# STC89LE.net
KiCad netlist of a schematic drawn in Altium Designer
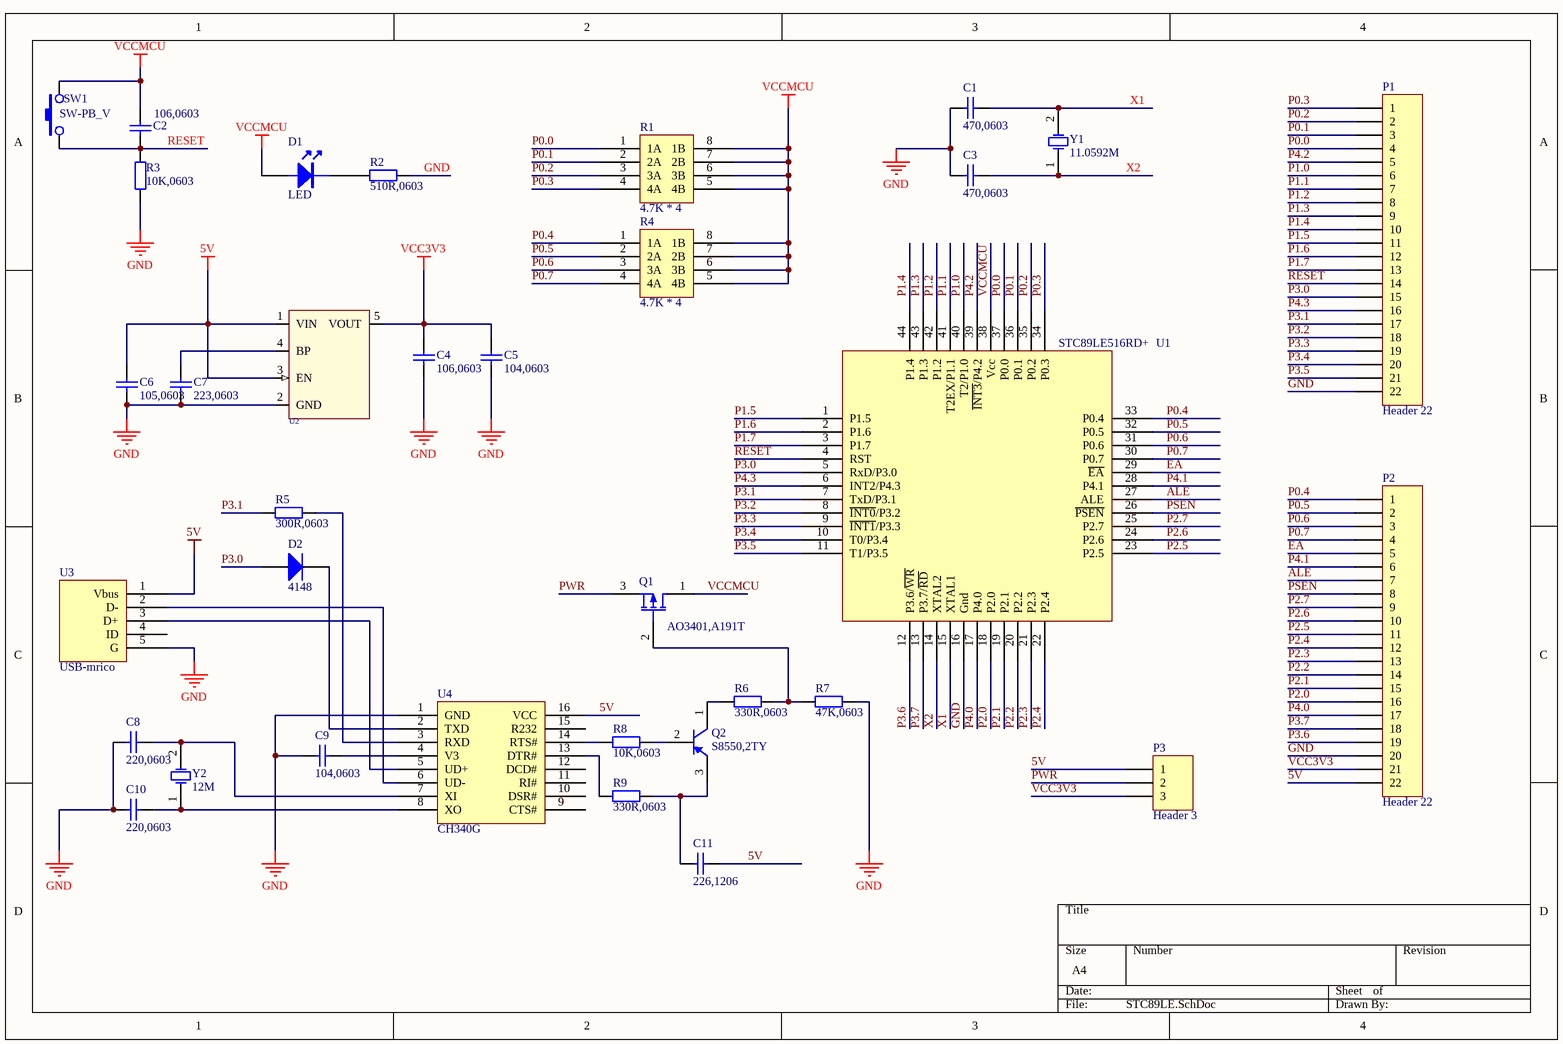
[diagram p0: STC89LE.SchDoc]

(export (version "E")
  (design (tool "Eeschema 10.0.6"))
  (components
    (comp (ref "C1")
      (value "470,0603")
      (footprint "C 0603")
      (description "Capacitor")
      (fields (field (name "PUBLISHER") "Altium Limited"))
      (libsource (lib "STM32F103C8T6") (part "Cap"))
    )
    (comp (ref "C2")
      (value "106,0603")
      (footprint "C 0603")
      (description "Capacitor")
      (fields (field (name "PUBLISHER") "Altium Limited"))
      (libsource (lib "STM32F103C8T6") (part "Cap"))
    )
    (comp (ref "C3")
      (value "470,0603")
      (footprint "C 0603")
      (description "Capacitor")
      (fields (field (name "PUBLISHER") "Altium Limited"))
      (libsource (lib "STM32F103C8T6") (part "Cap"))
    )
    (comp (ref "C4")
      (value "106,0603")
      (footprint "C 0603")
      (description "Capacitor")
      (fields (field (name "PUBLISHER") "Altium Limited"))
      (libsource (lib "STM32F103C8T6") (part "Cap"))
    )
    (comp (ref "C5")
      (value "104,0603")
      (footprint "C 0603")
      (description "Capacitor")
      (fields (field (name "PUBLISHER") "Altium Limited"))
      (libsource (lib "STM32F103C8T6") (part "Cap"))
    )
    (comp (ref "C6")
      (value "105,0603")
      (footprint "C 0603")
      (description "Capacitor")
      (fields (field (name "PUBLISHER") "Altium Limited"))
      (libsource (lib "STM32F103C8T6") (part "Cap"))
    )
    (comp (ref "C7")
      (value "223,0603")
      (footprint "C 0603")
      (description "Capacitor")
      (fields (field (name "PUBLISHER") "Altium Limited"))
      (libsource (lib "STM32F103C8T6") (part "Cap"))
    )
    (comp (ref "C8")
      (value "220,0603")
      (footprint "C 0603")
      (description "Capacitor")
      (fields (field (name "PUBLISHER") "Altium Limited"))
      (libsource (lib "STM32F103C8T6") (part "Cap"))
    )
    (comp (ref "C9")
      (value "104,0603")
      (footprint "C 0603")
      (description "Capacitor")
      (fields (field (name "PUBLISHER") "Altium Limited"))
      (libsource (lib "STM32F103C8T6") (part "Cap"))
    )
    (comp (ref "C10")
      (value "220,0603")
      (footprint "C 0603")
      (description "Capacitor")
      (fields (field (name "PUBLISHER") "Altium Limited"))
      (libsource (lib "STM32F103C8T6") (part "Cap"))
    )
    (comp (ref "C11")
      (value "226,1206")
      (footprint "C 3216")
      (description "Capacitor")
      (fields (field (name "PUBLISHER") "Altium Limited"))
      (libsource (lib "STM32F103C8T6") (part "Cap"))
    )
    (comp (ref "D1") (value "LED") (footprint "LED 0805G") (libsource (lib "STM32F103C8T6") (part "LED")))
    (comp (ref "D2")
      (value "4148")
      (footprint "DSO-C2/G1.6")
      (description "1 Amp General Purpose Rectifier")
      (fields (field (name "PUBLISHER") "Altium Limited"))
      (libsource (lib "Miscellaneous Devices") (part "Diode 1N4005"))
    )
    (comp (ref "P1")
      (value "Header 22")
      (footprint "HDR1X22")
      (description "Header, 22-Pin")
      (fields (field (name "PUBLISHER") "Altium Limited"))
      (libsource (lib "Miscellaneous Connectors") (part "Header 22"))
    )
    (comp (ref "P2")
      (value "Header 22")
      (footprint "HDR1X22")
      (description "Header, 22-Pin")
      (fields (field (name "PUBLISHER") "Altium Limited"))
      (libsource (lib "Miscellaneous Connectors") (part "Header 22"))
    )
    (comp (ref "P3")
      (value "Header 3")
      (footprint "HDR1X3")
      (description "Header, 3-Pin")
      (fields (field (name "PUBLISHER") "Altium Limited"))
      (libsource (lib "Miscellaneous Connectors") (part "Header 3"))
    )
    (comp (ref "Q1")
      (value "AO3401,A191T")
      (footprint "SOT23-3-MOS")
      (description "P-Channel MOSFET")
      (fields (field (name "PUBLISHER") "Altium Limited"))
      (libsource (lib "Miscellaneous Devices") (part "MOSFET-P"))
    )
    (comp (ref "Q2")
      (value "S8550,2TY")
      (footprint "SOT23-3-BJT")
      (description "PNP Bipolar Transistor")
      (fields (field (name "PUBLISHER") "Altium Limited"))
      (libsource (lib "Miscellaneous Devices") (part "PNP"))
    )
    (comp (ref "R1") (value "4.7K * 4") (footprint "8P4R 0603") (libsource (lib "PCB") (part "Res1")))
    (comp (ref "R2")
      (value "510R,0603")
      (footprint "R 0603")
      (description "Resistor")
      (fields (field (name "PUBLISHER") "Altium Limited"))
      (libsource (lib "") (part "Res2_1"))
    )
    (comp (ref "R3")
      (value "10K,0603")
      (footprint "R 0603")
      (description "Resistor")
      (fields (field (name "PUBLISHER") "Altium Limited"))
      (libsource (lib "") (part "Res2_2"))
    )
    (comp (ref "R4") (value "4.7K * 4") (footprint "8P4R 0603") (libsource (lib "PCB") (part "Res1")))
    (comp (ref "R5")
      (value "300R,0603")
      (footprint "R 0603")
      (description "Resistor")
      (fields (field (name "PUBLISHER") "Altium Limited"))
      (libsource (lib "STM32F103C8T6") (part "Res2"))
    )
    (comp (ref "R6")
      (value "330R,0603")
      (footprint "R 0603")
      (description "Resistor")
      (fields (field (name "PUBLISHER") "Altium Limited"))
      (libsource (lib "STM32F103C8T6") (part "Res2"))
    )
    (comp (ref "R7")
      (value "47K,0603")
      (footprint "R 0603")
      (description "Resistor")
      (fields (field (name "PUBLISHER") "Altium Limited"))
      (libsource (lib "STM32F103C8T6") (part "Res2"))
    )
    (comp (ref "R8")
      (value "10K,0603")
      (footprint "R 0603")
      (description "Resistor")
      (fields (field (name "PUBLISHER") "Altium Limited"))
      (libsource (lib "STM32F103C8T6") (part "Res2"))
    )
    (comp (ref "R9")
      (value "330R,0603")
      (footprint "R 0603")
      (description "Resistor")
      (fields (field (name "PUBLISHER") "Altium Limited"))
      (libsource (lib "STM32F103C8T6") (part "Res2"))
    )
    (comp (ref "SW1")
      (value "SW-PB_V")
      (footprint "TSW SMD-3*6*2.5")
      (description "SWITCH")
      (libsource (lib "STM32F103C8T6") (part "SW-PB_V"))
    )
    (comp (ref "U1")
      (value "STC89LE516RD+")
      (footprint "LQFP44")
      (libsource (lib "PCB") (part "STC89LE516RD+"))
    )
    (comp (ref "U2")
      (value "RT9193")
      (footprint "SOT23-5L")
      (fields (field (name "ICA_PARTNUM") "$$2191094$$RT9193-15CU5") (field (name "PART NUMBER") "TMP-13"))
      (libsource (lib "STM32F103C8T6") (part "RT9193X_5P"))
    )
    (comp (ref "U3")
      (value "USB-mrico")
      (footprint "USB-micro_B")
      (libsource (lib "PCB_Project_4") (part "usb-STM"))
    )
    (comp (ref "U4") (value "CH340G") (footprint "SOP16") (libsource (lib "PCB") (part "CH340G")))
    (comp (ref "Y1")
      (value "11.0592M")
      (footprint "STM32F103C8T6核心板:XTAL-5032")
      (description "Crystal Oscillator")
      (fields (field (name "PUBLISHER") "Altium Limited"))
      (libsource (lib "PCB_Project_4") (part "XTAL"))
    )
    (comp (ref "Y2")
      (value "12M")
      (footprint "STM32F103C8T6核心板:XTAL-5032")
      (description "Crystal Oscillator")
      (fields (field (name "PUBLISHER") "Altium Limited"))
      (libsource (lib "PCB_Project_4") (part "XTAL"))
    )
  )
  (nets
    (net (code "1") (name "/ALE") (class "Default")
      (node (ref "P2") (pin "7") (pinfunction "7_7") (pintype "passive"))
      (node (ref "U1") (pin "27") (pinfunction "ALE_27") (pintype "passive"))
    )
    (net (code "2") (name "/EA") (class "Default")
      (node (ref "P2") (pin "5") (pinfunction "5_5") (pintype "passive"))
      (node (ref "U1") (pin "29") (pinfunction "~{EA}_29") (pintype "passive"))
    )
    (net (code "3") (name "/P0.0") (class "Default")
      (node (ref "P1") (pin "4") (pinfunction "4_4") (pintype "passive"))
      (node (ref "R1") (pin "1") (pinfunction "1A_1") (pintype "passive"))
      (node (ref "U1") (pin "37") (pinfunction "P0.0_37") (pintype "passive"))
    )
    (net (code "4") (name "/P0.1") (class "Default")
      (node (ref "P1") (pin "3") (pinfunction "3_3") (pintype "passive"))
      (node (ref "R1") (pin "2") (pinfunction "2A_2") (pintype "passive"))
      (node (ref "U1") (pin "36") (pinfunction "P0.1_36") (pintype "passive"))
    )
    (net (code "5") (name "/P0.2") (class "Default")
      (node (ref "P1") (pin "2") (pinfunction "2_2") (pintype "passive"))
      (node (ref "R1") (pin "3") (pinfunction "3A_3") (pintype "passive"))
      (node (ref "U1") (pin "35") (pinfunction "P0.2_35") (pintype "passive"))
    )
    (net (code "6") (name "/P0.3") (class "Default")
      (node (ref "P1") (pin "1") (pinfunction "1_1") (pintype "passive"))
      (node (ref "R1") (pin "4") (pinfunction "4A_4") (pintype "passive"))
      (node (ref "U1") (pin "34") (pinfunction "P0.3_34") (pintype "passive"))
    )
    (net (code "7") (name "/P0.4") (class "Default")
      (node (ref "P2") (pin "1") (pinfunction "1_1") (pintype "passive"))
      (node (ref "R4") (pin "1") (pinfunction "1A_1") (pintype "passive"))
      (node (ref "U1") (pin "33") (pinfunction "P0.4_33") (pintype "passive"))
    )
    (net (code "8") (name "/P0.5") (class "Default")
      (node (ref "P2") (pin "2") (pinfunction "2_2") (pintype "passive"))
      (node (ref "R4") (pin "2") (pinfunction "2A_2") (pintype "passive"))
      (node (ref "U1") (pin "32") (pinfunction "P0.5_32") (pintype "passive"))
    )
    (net (code "9") (name "/P0.6") (class "Default")
      (node (ref "P2") (pin "3") (pinfunction "3_3") (pintype "passive"))
      (node (ref "R4") (pin "3") (pinfunction "3A_3") (pintype "passive"))
      (node (ref "U1") (pin "31") (pinfunction "P0.6_31") (pintype "passive"))
    )
    (net (code "10") (name "/P0.7") (class "Default")
      (node (ref "P2") (pin "4") (pinfunction "4_4") (pintype "passive"))
      (node (ref "R4") (pin "4") (pinfunction "4A_4") (pintype "passive"))
      (node (ref "U1") (pin "30") (pinfunction "P0.7_30") (pintype "passive"))
    )
    (net (code "11") (name "/P1.0") (class "Default")
      (node (ref "P1") (pin "6") (pinfunction "6_6") (pintype "passive"))
      (node (ref "U1") (pin "40") (pinfunction "T2/P1.0_40") (pintype "passive"))
    )
    (net (code "12") (name "/P1.1") (class "Default")
      (node (ref "P1") (pin "7") (pinfunction "7_7") (pintype "passive"))
      (node (ref "U1") (pin "41") (pinfunction "T2EX/P1.1_41") (pintype "passive"))
    )
    (net (code "13") (name "/P1.2") (class "Default")
      (node (ref "P1") (pin "8") (pinfunction "8_8") (pintype "passive"))
      (node (ref "U1") (pin "42") (pinfunction "P1.2_42") (pintype "passive"))
    )
    (net (code "14") (name "/P1.3") (class "Default")
      (node (ref "P1") (pin "9") (pinfunction "9_9") (pintype "passive"))
      (node (ref "U1") (pin "43") (pinfunction "P1.3_43") (pintype "passive"))
    )
    (net (code "15") (name "/P1.4") (class "Default")
      (node (ref "P1") (pin "10") (pinfunction "10_10") (pintype "passive"))
      (node (ref "U1") (pin "44") (pinfunction "P1.4_44") (pintype "passive"))
    )
    (net (code "16") (name "/P1.5") (class "Default")
      (node (ref "P1") (pin "11") (pinfunction "11_11") (pintype "passive"))
      (node (ref "U1") (pin "1") (pinfunction "P1.5_1") (pintype "passive"))
    )
    (net (code "17") (name "/P1.6") (class "Default")
      (node (ref "P1") (pin "12") (pinfunction "12_12") (pintype "passive"))
      (node (ref "U1") (pin "2") (pinfunction "P1.6_2") (pintype "passive"))
    )
    (net (code "18") (name "/P1.7") (class "Default")
      (node (ref "P1") (pin "13") (pinfunction "13_13") (pintype "passive"))
      (node (ref "U1") (pin "3") (pinfunction "P1.7_3") (pintype "passive"))
    )
    (net (code "19") (name "/P2.0") (class "Default")
      (node (ref "P2") (pin "16") (pinfunction "16_16") (pintype "passive"))
      (node (ref "U1") (pin "18") (pinfunction "P2.0_18") (pintype "passive"))
    )
    (net (code "20") (name "/P2.1") (class "Default")
      (node (ref "P2") (pin "15") (pinfunction "15_15") (pintype "passive"))
      (node (ref "U1") (pin "19") (pinfunction "P2.1_19") (pintype "passive"))
    )
    (net (code "21") (name "/P2.2") (class "Default")
      (node (ref "P2") (pin "14") (pinfunction "14_14") (pintype "passive"))
      (node (ref "U1") (pin "20") (pinfunction "P2.2_20") (pintype "passive"))
    )
    (net (code "22") (name "/P2.3") (class "Default")
      (node (ref "P2") (pin "13") (pinfunction "13_13") (pintype "passive"))
      (node (ref "U1") (pin "21") (pinfunction "P2.3_21") (pintype "passive"))
    )
    (net (code "23") (name "/P2.4") (class "Default")
      (node (ref "P2") (pin "12") (pinfunction "12_12") (pintype "passive"))
      (node (ref "U1") (pin "22") (pinfunction "P2.4_22") (pintype "passive"))
    )
    (net (code "24") (name "/P2.5") (class "Default")
      (node (ref "P2") (pin "11") (pinfunction "11_11") (pintype "passive"))
      (node (ref "U1") (pin "23") (pinfunction "P2.5_23") (pintype "passive"))
    )
    (net (code "25") (name "/P2.6") (class "Default")
      (node (ref "P2") (pin "10") (pinfunction "10_10") (pintype "passive"))
      (node (ref "U1") (pin "24") (pinfunction "P2.6_24") (pintype "passive"))
    )
    (net (code "26") (name "/P2.7") (class "Default")
      (node (ref "P2") (pin "9") (pinfunction "9_9") (pintype "passive"))
      (node (ref "U1") (pin "25") (pinfunction "P2.7_25") (pintype "passive"))
    )
    (net (code "27") (name "/P3.0") (class "Default")
      (node (ref "D2") (pin "1") (pinfunction "A_1") (pintype "passive"))
      (node (ref "P1") (pin "15") (pinfunction "15_15") (pintype "passive"))
      (node (ref "U1") (pin "5") (pinfunction "RxD/P3.0_5") (pintype "passive"))
    )
    (net (code "28") (name "/P3.1") (class "Default")
      (node (ref "P1") (pin "17") (pinfunction "17_17") (pintype "passive"))
      (node (ref "R5") (pin "2") (pinfunction "2_2") (pintype "passive"))
      (node (ref "U1") (pin "7") (pinfunction "TxD/P3.1_7") (pintype "passive"))
    )
    (net (code "29") (name "/P3.2") (class "Default")
      (node (ref "P1") (pin "18") (pinfunction "18_18") (pintype "passive"))
      (node (ref "U1") (pin "8") (pinfunction "~{INT0}/P3.2_8") (pintype "passive"))
    )
    (net (code "30") (name "/P3.3") (class "Default")
      (node (ref "P1") (pin "19") (pinfunction "19_19") (pintype "passive"))
      (node (ref "U1") (pin "9") (pinfunction "~{INT1}/P3.3_9") (pintype "passive"))
    )
    (net (code "31") (name "/P3.4") (class "Default")
      (node (ref "P1") (pin "20") (pinfunction "20_20") (pintype "passive"))
      (node (ref "U1") (pin "10") (pinfunction "T0/P3.4_10") (pintype "passive"))
    )
    (net (code "32") (name "/P3.5") (class "Default")
      (node (ref "P1") (pin "21") (pinfunction "21_21") (pintype "passive"))
      (node (ref "U1") (pin "11") (pinfunction "T1/P3.5_11") (pintype "passive"))
    )
    (net (code "33") (name "/P3.6") (class "Default")
      (node (ref "P2") (pin "19") (pinfunction "19_19") (pintype "passive"))
      (node (ref "U1") (pin "12") (pinfunction "P3.6/~{WR}_12") (pintype "passive"))
    )
    (net (code "34") (name "/P3.7") (class "Default")
      (node (ref "P2") (pin "18") (pinfunction "18_18") (pintype "passive"))
      (node (ref "U1") (pin "13") (pinfunction "P3.7/~{RD}_13") (pintype "passive"))
    )
    (net (code "35") (name "/P4.0") (class "Default")
      (node (ref "P2") (pin "17") (pinfunction "17_17") (pintype "passive"))
      (node (ref "U1") (pin "17") (pinfunction "P4.0_17") (pintype "passive"))
    )
    (net (code "36") (name "/P4.1") (class "Default")
      (node (ref "P2") (pin "6") (pinfunction "6_6") (pintype "passive"))
      (node (ref "U1") (pin "28") (pinfunction "P4.1_28") (pintype "passive"))
    )
    (net (code "37") (name "/P4.2") (class "Default")
      (node (ref "P1") (pin "5") (pinfunction "5_5") (pintype "passive"))
      (node (ref "U1") (pin "39") (pinfunction "~{INT3}/P4.2_39") (pintype "passive"))
    )
    (net (code "38") (name "/P4.3") (class "Default")
      (node (ref "P1") (pin "16") (pinfunction "16_16") (pintype "passive"))
      (node (ref "U1") (pin "6") (pinfunction "INT2/P4.3_6") (pintype "passive"))
    )
    (net (code "39") (name "/PSEN") (class "Default")
      (node (ref "P2") (pin "8") (pinfunction "8_8") (pintype "passive"))
      (node (ref "U1") (pin "26") (pinfunction "~{PSEN}_26") (pintype "passive"))
    )
    (net (code "40") (name "/PWR") (class "Default")
      (node (ref "P3") (pin "2") (pinfunction "2_2") (pintype "passive"))
      (node (ref "Q1") (pin "3") (pinfunction "S_3") (pintype "passive"))
    )
    (net (code "41") (name "/RESET") (class "Default")
      (node (ref "C2") (pin "1") (pinfunction "1_1") (pintype "passive"))
      (node (ref "P1") (pin "14") (pinfunction "14_14") (pintype "passive"))
      (node (ref "R3") (pin "2") (pinfunction "2_2") (pintype "passive"))
      (node (ref "SW1") (pin "1") (pinfunction "1_1") (pintype "passive"))
      (node (ref "U1") (pin "4") (pinfunction "RST_4") (pintype "passive"))
    )
    (net (code "42") (name "/X1") (class "Default")
      (node (ref "C1") (pin "1") (pinfunction "1_1") (pintype "passive"))
      (node (ref "U1") (pin "15") (pinfunction "XTAL1_15") (pintype "passive"))
      (node (ref "Y1") (pin "2") (pinfunction "OSC2_2") (pintype "passive"))
    )
    (net (code "43") (name "/X2") (class "Default")
      (node (ref "C3") (pin "1") (pinfunction "1_1") (pintype "passive"))
      (node (ref "U1") (pin "14") (pinfunction "XTAL2_14") (pintype "passive"))
      (node (ref "Y1") (pin "1") (pinfunction "OSC1_1") (pintype "passive"))
    )
    (net (code "44") (name "5V") (class "Default")
      (node (ref "C11") (pin "1") (pinfunction "1_1") (pintype "passive"))
      (node (ref "C6") (pin "2") (pinfunction "2_2") (pintype "passive"))
      (node (ref "P2") (pin "22") (pinfunction "22_22") (pintype "passive"))
      (node (ref "P3") (pin "1") (pinfunction "1_1") (pintype "passive"))
      (node (ref "U2") (pin "1") (pinfunction "VIN_1") (pintype "power_in"))
      (node (ref "U2") (pin "3") (pinfunction "EN_3") (pintype "input"))
      (node (ref "U3") (pin "1") (pinfunction "Vbus_1") (pintype "passive"))
      (node (ref "U4") (pin "16") (pinfunction "VCC_16") (pintype "passive"))
    )
    (net (code "45") (name "GND") (class "Default")
      (node (ref "C1") (pin "2") (pinfunction "2_2") (pintype "passive"))
      (node (ref "C10") (pin "2") (pinfunction "2_2") (pintype "passive"))
      (node (ref "C3") (pin "2") (pinfunction "2_2") (pintype "passive"))
      (node (ref "C4") (pin "2") (pinfunction "2_2") (pintype "passive"))
      (node (ref "C5") (pin "1") (pinfunction "1_1") (pintype "passive"))
      (node (ref "C6") (pin "1") (pinfunction "1_1") (pintype "passive"))
      (node (ref "C7") (pin "1") (pinfunction "1_1") (pintype "passive"))
      (node (ref "C8") (pin "2") (pinfunction "2_2") (pintype "passive"))
      (node (ref "C9") (pin "2") (pinfunction "2_2") (pintype "passive"))
      (node (ref "P1") (pin "22") (pinfunction "22_22") (pintype "passive"))
      (node (ref "P2") (pin "20") (pinfunction "20_20") (pintype "passive"))
      (node (ref "R2") (pin "2") (pinfunction "2_2") (pintype "passive"))
      (node (ref "R3") (pin "1") (pinfunction "1_1") (pintype "passive"))
      (node (ref "R7") (pin "1") (pinfunction "1_1") (pintype "passive"))
      (node (ref "U1") (pin "16") (pinfunction "Gnd_16") (pintype "passive"))
      (node (ref "U2") (pin "2") (pinfunction "GND_2") (pintype "power_in"))
      (node (ref "U3") (pin "5") (pinfunction "G_5") (pintype "passive"))
      (node (ref "U4") (pin "1") (pinfunction "GND_1") (pintype "passive"))
    )
    (net (code "46") (name "Net-(D1-Pad2)") (class "Default")
      (node (ref "D1") (pin "2") (pinfunction "2_2") (pintype "passive"))
      (node (ref "R2") (pin "1") (pinfunction "1_1") (pintype "passive"))
    )
    (net (code "47") (name "Net-(D2-K)") (class "Default")
      (node (ref "D2") (pin "2") (pinfunction "K_2") (pintype "passive"))
      (node (ref "U4") (pin "2") (pinfunction "TXD_2") (pintype "passive"))
    )
    (net (code "48") (name "Net-(Q1-G)") (class "Default")
      (node (ref "Q1") (pin "2") (pinfunction "G_2") (pintype "passive"))
      (node (ref "R6") (pin "1") (pinfunction "1_1") (pintype "passive"))
      (node (ref "R7") (pin "2") (pinfunction "2_2") (pintype "passive"))
    )
    (net (code "49") (name "Net-(Q2-B)") (class "Default")
      (node (ref "Q2") (pin "2") (pinfunction "B_2") (pintype "passive"))
      (node (ref "R8") (pin "1") (pinfunction "1_1") (pintype "passive"))
    )
    (net (code "50") (name "Net-(Q2-C)") (class "Default")
      (node (ref "Q2") (pin "1") (pinfunction "C_1") (pintype "passive"))
      (node (ref "R6") (pin "2") (pinfunction "2_2") (pintype "passive"))
    )
    (net (code "51") (name "Net-(Q2-E)") (class "Default")
      (node (ref "C11") (pin "2") (pinfunction "2_2") (pintype "passive"))
      (node (ref "Q2") (pin "3") (pinfunction "E_3") (pintype "passive"))
      (node (ref "R9") (pin "1") (pinfunction "1_1") (pintype "passive"))
    )
    (net (code "52") (name "Net-(U2-BP)") (class "Default")
      (node (ref "C7") (pin "2") (pinfunction "2_2") (pintype "passive"))
      (node (ref "U2") (pin "4") (pinfunction "BP_4") (pintype "passive"))
    )
    (net (code "53") (name "Net-(U3-D+)") (class "Default")
      (node (ref "U3") (pin "3") (pinfunction "D+_3") (pintype "passive"))
      (node (ref "U4") (pin "5") (pinfunction "UD+_5") (pintype "passive"))
    )
    (net (code "54") (name "Net-(U3-D-)") (class "Default")
      (node (ref "U3") (pin "2") (pinfunction "D-_2") (pintype "passive"))
      (node (ref "U4") (pin "6") (pinfunction "UD-_6") (pintype "passive"))
    )
    (net (code "55") (name "Net-(U4-DTR#)") (class "Default")
      (node (ref "R9") (pin "2") (pinfunction "2_2") (pintype "passive"))
      (node (ref "U4") (pin "13") (pinfunction "DTR#_13") (pintype "passive"))
    )
    (net (code "56") (name "Net-(U4-RTS#)") (class "Default")
      (node (ref "R8") (pin "2") (pinfunction "2_2") (pintype "passive"))
      (node (ref "U4") (pin "14") (pinfunction "RTS#_14") (pintype "passive"))
    )
    (net (code "57") (name "Net-(U4-RXD)") (class "Default")
      (node (ref "R5") (pin "1") (pinfunction "1_1") (pintype "passive"))
      (node (ref "U4") (pin "3") (pinfunction "RXD_3") (pintype "passive"))
    )
    (net (code "58") (name "Net-(U4-V3)") (class "Default")
      (node (ref "C9") (pin "1") (pinfunction "1_1") (pintype "passive"))
      (node (ref "U4") (pin "4") (pinfunction "V3_4") (pintype "passive"))
    )
    (net (code "59") (name "Net-(U4-XI)") (class "Default")
      (node (ref "C8") (pin "1") (pinfunction "1_1") (pintype "passive"))
      (node (ref "U4") (pin "7") (pinfunction "XI_7") (pintype "passive"))
      (node (ref "Y2") (pin "2") (pinfunction "OSC2_2") (pintype "passive"))
    )
    (net (code "60") (name "Net-(U4-XO)") (class "Default")
      (node (ref "C10") (pin "1") (pinfunction "1_1") (pintype "passive"))
      (node (ref "U4") (pin "8") (pinfunction "XO_8") (pintype "passive"))
      (node (ref "Y2") (pin "1") (pinfunction "OSC1_1") (pintype "passive"))
    )
    (net (code "61") (name "VCC3V3") (class "Default")
      (node (ref "C4") (pin "1") (pinfunction "1_1") (pintype "passive"))
      (node (ref "C5") (pin "2") (pinfunction "2_2") (pintype "passive"))
      (node (ref "P2") (pin "21") (pinfunction "21_21") (pintype "passive"))
      (node (ref "P3") (pin "3") (pinfunction "3_3") (pintype "passive"))
      (node (ref "U2") (pin "5") (pinfunction "VOUT_5") (pintype "power_in"))
    )
    (net (code "62") (name "VCCMCU") (class "Default")
      (node (ref "C2") (pin "2") (pinfunction "2_2") (pintype "passive"))
      (node (ref "D1") (pin "1") (pinfunction "1_1") (pintype "passive"))
      (node (ref "Q1") (pin "1") (pinfunction "D_1") (pintype "passive"))
      (node (ref "R1") (pin "5") (pinfunction "4B_5") (pintype "passive"))
      (node (ref "R1") (pin "6") (pinfunction "3B_6") (pintype "passive"))
      (node (ref "R1") (pin "7") (pinfunction "2B_7") (pintype "passive"))
      (node (ref "R1") (pin "8") (pinfunction "1B_8") (pintype "passive"))
      (node (ref "R4") (pin "5") (pinfunction "4B_5") (pintype "passive"))
      (node (ref "R4") (pin "6") (pinfunction "3B_6") (pintype "passive"))
      (node (ref "R4") (pin "7") (pinfunction "2B_7") (pintype "passive"))
      (node (ref "R4") (pin "8") (pinfunction "1B_8") (pintype "passive"))
      (node (ref "SW1") (pin "2") (pinfunction "2_2") (pintype "passive"))
      (node (ref "U1") (pin "38") (pinfunction "Vcc_38") (pintype "passive"))
    )
    (net (code "63") (name "unconnected-(U3-ID-Pad4)") (class "Default")
      (node (ref "U3") (pin "4") (pinfunction "ID_4") (pintype "passive"))
    )
    (net (code "64") (name "unconnected-(U4-CTS#-Pad9)") (class "Default")
      (node (ref "U4") (pin "9") (pinfunction "CTS#_9") (pintype "passive"))
    )
    (net (code "65") (name "unconnected-(U4-DCD#-Pad12)") (class "Default")
      (node (ref "U4") (pin "12") (pinfunction "DCD#_12") (pintype "passive"))
    )
    (net (code "66") (name "unconnected-(U4-DSR#-Pad10)") (class "Default")
      (node (ref "U4") (pin "10") (pinfunction "DSR#_10") (pintype "passive"))
    )
    (net (code "67") (name "unconnected-(U4-R232-Pad15)") (class "Default")
      (node (ref "U4") (pin "15") (pinfunction "R232_15") (pintype "passive"))
    )
    (net (code "68") (name "unconnected-(U4-RI#-Pad11)") (class "Default")
      (node (ref "U4") (pin "11") (pinfunction "RI#_11") (pintype "passive"))
    )
  )
)
